# Power_Management.net
KiCad netlist of a schematic drawn in Altium Designer
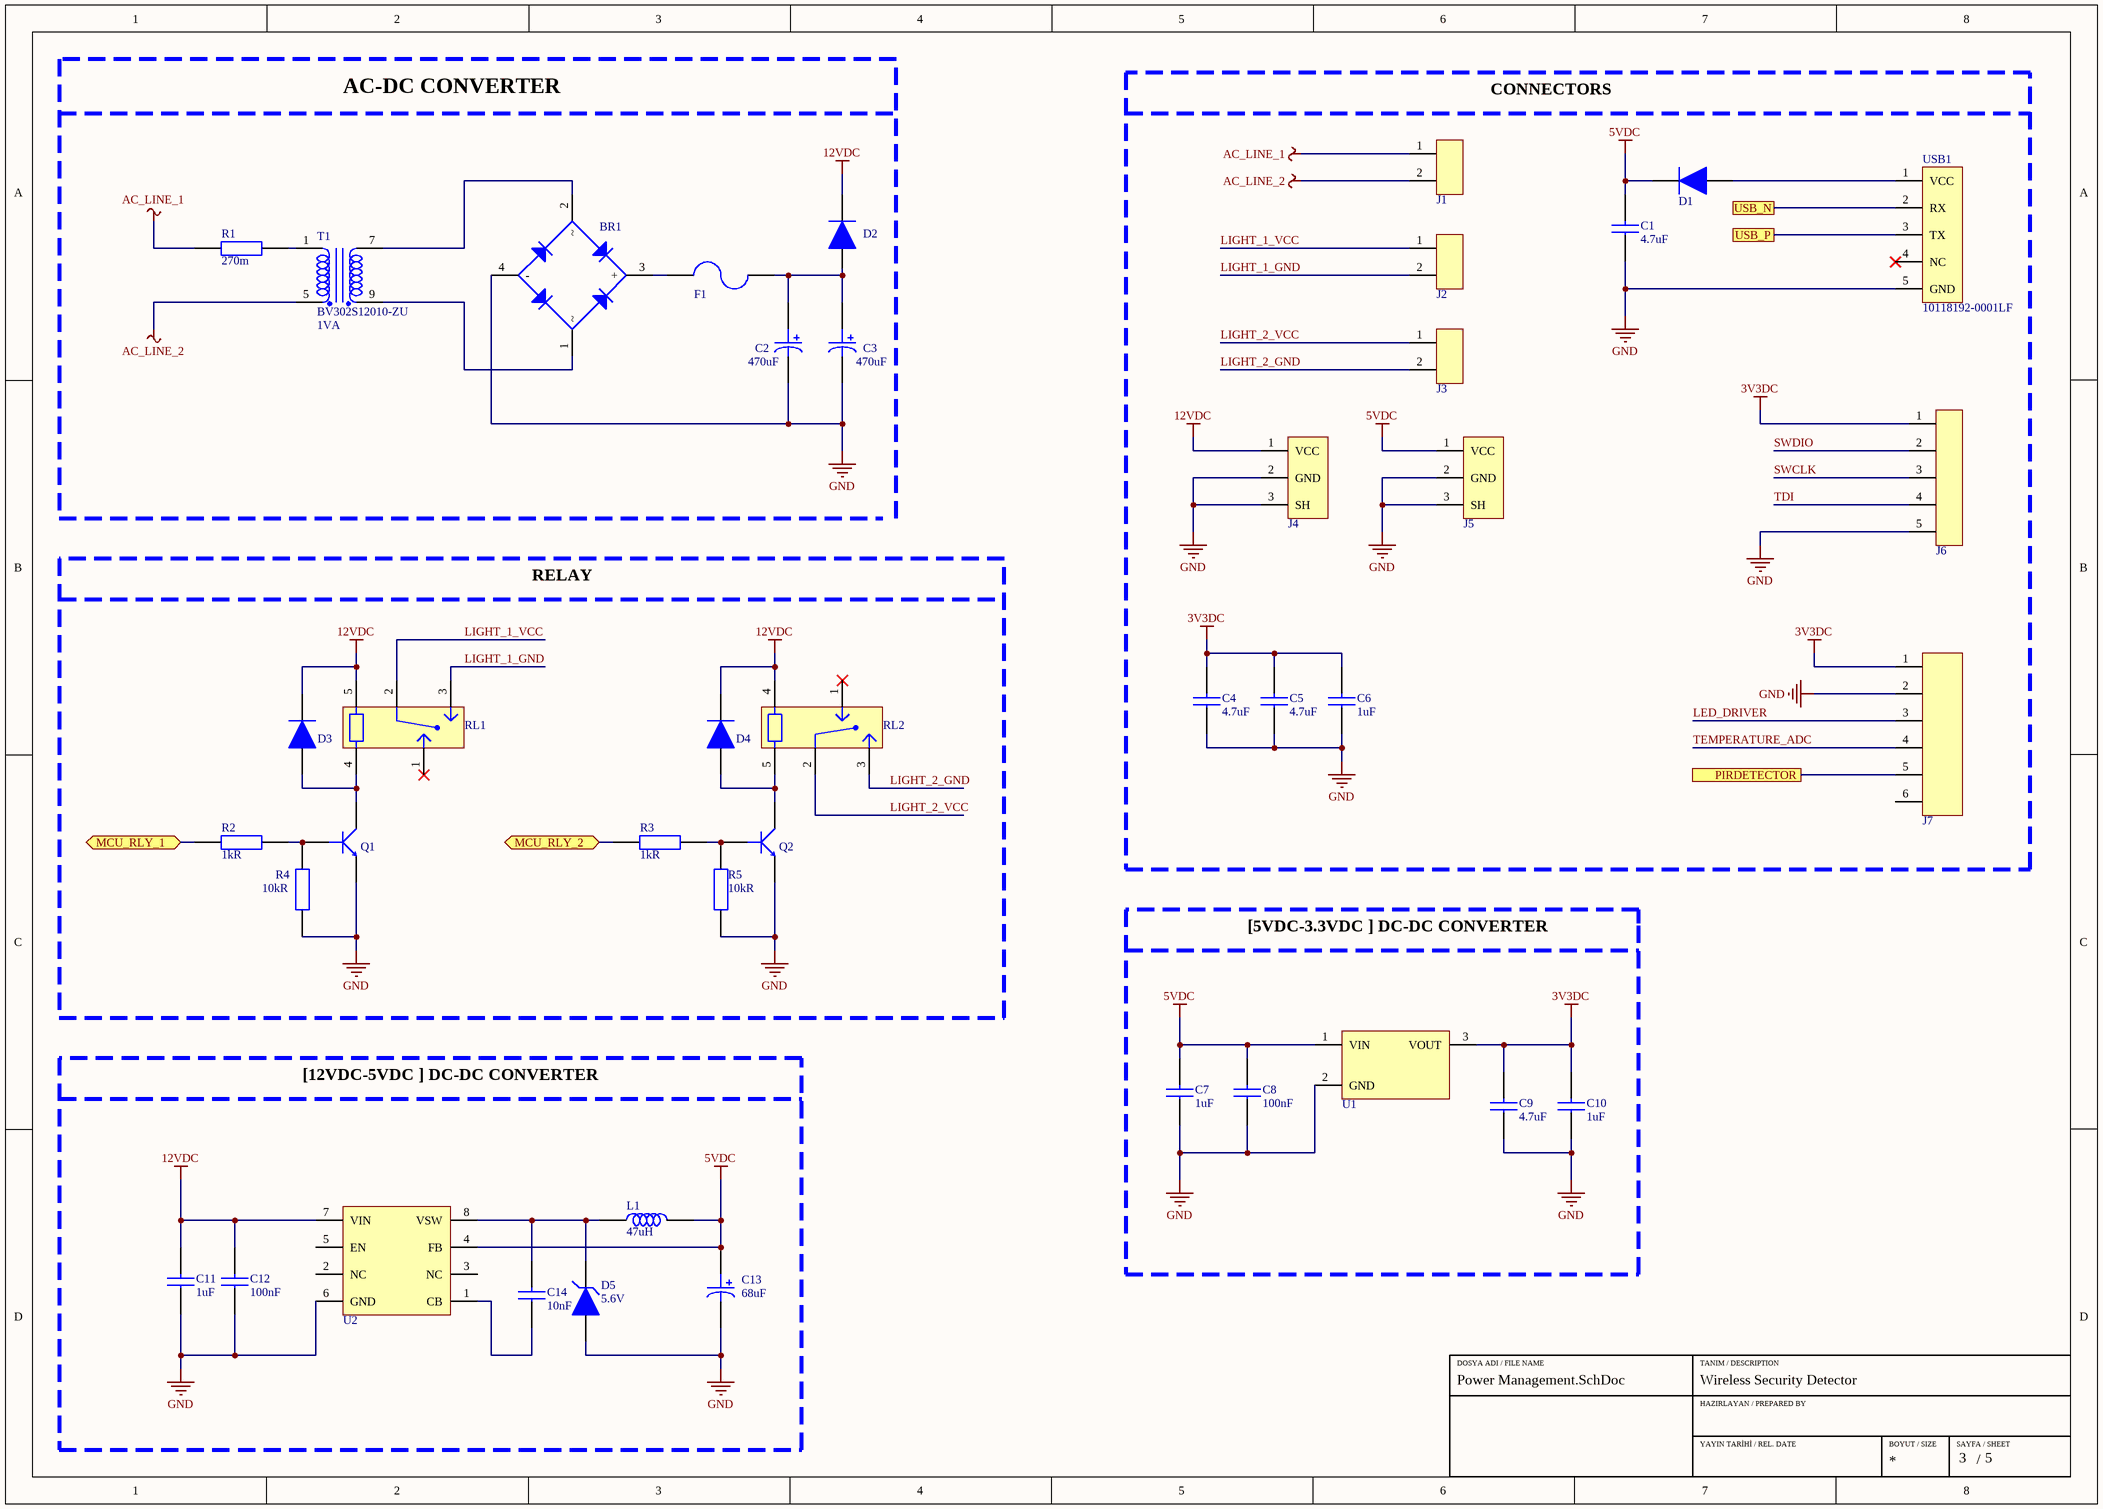
[diagram p0: Power Management.SchDoc]

(export (version "E")
  (design (tool "Eeschema 10.0.6"))
  (components
    (comp (ref "BR1")
      (value "DB105STR")
      (footprint "DB105STR")
      (description "Bridge Diode AC-DC")
      (fields (field (name "MANUFACTURER") "Sangdest Microelectronics") (field (name "DESIGNED BY") "BERK"))
      (libsource (lib "SECURITY_CAM") (part "DB105STR"))
    )
    (comp (ref "C1")
      (value "CL21A475KAQNNNE")
      (footprint "CAP_0805")
      (description "CAP CER 4.7uF %10 0805")
      (fields
        (field (name "MANUFACTURER") "Samsung")
        (field (name "TOLERANCE") "10%")
        (field (name "CAPACITANCE") "4.7uF")
        (field (name "DESIGNED BY") "BERK")
      )
      (libsource (lib "SECURITY_CAM") (part "CAP CER 4.7uF 0805"))
    )
    (comp (ref "C2")
      (value "ESH477M050AH4AA")
      (footprint "CAP_RADIAL_D10_P5")
      (description "CAP ALU ELEC 470uF 50V RADIAL")
      (fields
        (field (name "MANUFACTURER") "KEMET")
        (field (name "TOLERANCE") "20%")
        (field (name "CAPACITANCE") "470uF")
        (field (name "DESIGNED BY") "BERK")
      )
      (libsource (lib "SECURITY_CAM") (part "CAP ALU ELEC 470uF 50V"))
    )
    (comp (ref "C3")
      (value "ESH477M050AH4AA")
      (footprint "CAP_RADIAL_D10_P5")
      (description "CAP ALU ELEC 470uF 50V RADIAL")
      (fields
        (field (name "MANUFACTURER") "KEMET")
        (field (name "TOLERANCE") "20%")
        (field (name "CAPACITANCE") "470uF")
        (field (name "DESIGNED BY") "BERK")
      )
      (libsource (lib "SECURITY_CAM") (part "CAP ALU ELEC 470uF 50V"))
    )
    (comp (ref "C4")
      (value "CL21A475KAQNNNE")
      (footprint "CAP_0805")
      (description "CAP CER 4.7uF %10 0805")
      (fields
        (field (name "MANUFACTURER") "Samsung")
        (field (name "TOLERANCE") "10%")
        (field (name "CAPACITANCE") "4.7uF")
        (field (name "DESIGNED BY") "BERK")
      )
      (libsource (lib "SECURITY_CAM") (part "CAP CER 4.7uF 0805"))
    )
    (comp (ref "C5")
      (value "CL21A475KAQNNNE")
      (footprint "CAP_0805")
      (description "CAP CER 4.7uF %10 0805")
      (fields
        (field (name "MANUFACTURER") "Samsung")
        (field (name "TOLERANCE") "10%")
        (field (name "CAPACITANCE") "4.7uF")
        (field (name "DESIGNED BY") "BERK")
      )
      (libsource (lib "SECURITY_CAM") (part "CAP CER 4.7uF 0805"))
    )
    (comp (ref "C6")
      (value "CL21B105KBFNNNE")
      (footprint "CAP_0805")
      (description "CAP CER 1uF %10 0805")
      (fields
        (field (name "MANUFACTURER") "Samsung")
        (field (name "TOLERANCE") "10%")
        (field (name "CAPACITANCE") "1uF")
        (field (name "DESIGNED BY") "BERK")
      )
      (libsource (lib "SECURITY_CAM") (part "CAP CER 1uF 0805"))
    )
    (comp (ref "C7")
      (value "CL21B105KBFNNNE")
      (footprint "CAP_0805")
      (description "CAP CER 1uF %10 0805")
      (fields
        (field (name "MANUFACTURER") "Samsung")
        (field (name "TOLERANCE") "10%")
        (field (name "CAPACITANCE") "1uF")
        (field (name "DESIGNED BY") "BERK")
      )
      (libsource (lib "SECURITY_CAM") (part "CAP CER 1uF 0805"))
    )
    (comp (ref "C8")
      (value "C0603C104K5RACTU")
      (footprint "CAP_0603")
      (description "CAP CER 100nF %10 0603 SMD")
      (fields
        (field (name "MANUFACTURER") "KEMET")
        (field (name "TOLERANCE") "10%")
        (field (name "CAPACITANCE") "100nF")
        (field (name "DESIGNED BY") "BERK")
      )
      (libsource (lib "SECURITY_CAM") (part "CAP CER 100nF 0603"))
    )
    (comp (ref "C9")
      (value "CL21A475KAQNNNE")
      (footprint "CAP_0805")
      (description "CAP CER 4.7uF %10 0805")
      (fields
        (field (name "MANUFACTURER") "Samsung")
        (field (name "TOLERANCE") "10%")
        (field (name "CAPACITANCE") "4.7uF")
        (field (name "DESIGNED BY") "BERK")
      )
      (libsource (lib "SECURITY_CAM") (part "CAP CER 4.7uF 0805"))
    )
    (comp (ref "C10")
      (value "CL21B105KBFNNNE")
      (footprint "CAP_0805")
      (description "CAP CER 1uF %10 0805")
      (fields
        (field (name "MANUFACTURER") "Samsung")
        (field (name "TOLERANCE") "10%")
        (field (name "CAPACITANCE") "1uF")
        (field (name "DESIGNED BY") "BERK")
      )
      (libsource (lib "SECURITY_CAM") (part "CAP CER 1uF 0805"))
    )
    (comp (ref "C11")
      (value "CL21B105KBFNNNE")
      (footprint "CAP_0805")
      (description "CAP CER 1uF %10 0805")
      (fields
        (field (name "MANUFACTURER") "Samsung")
        (field (name "TOLERANCE") "10%")
        (field (name "CAPACITANCE") "1uF")
        (field (name "DESIGNED BY") "BERK")
      )
      (libsource (lib "SECURITY_CAM") (part "CAP CER 1uF 0805"))
    )
    (comp (ref "C12")
      (value "CL21B104KBCNNNC")
      (footprint "CAP_0805")
      (description "CAP CER 100nF %10 0805")
      (fields
        (field (name "MANUFACTURER") "Samsung")
        (field (name "TOLERANCE") "10%")
        (field (name "CAPACITANCE") "100nF")
        (field (name "DESIGNED BY") "BERK")
      )
      (libsource (lib "SECURITY_CAM") (part "CAP CER 100nF 0805"))
    )
    (comp (ref "C13")
      (value "EEV686M035A9HAA")
      (footprint "CAP_EEVseries")
      (description "Cap Aluminum Lytic 68uF 35V 20% (6.3 X 7.7mm) SMD 280mA 2000h 105C T/R")
      (fields
        (field (name "MANUFACTURER") "KEMET")
        (field (name "TOLERANCE") "20%")
        (field (name "CAPACITANCE") "68uF")
      )
      (libsource (lib "SECURITY_CAM") (part "CAP ALU 68uF"))
    )
    (comp (ref "C14")
      (value "0603B103K160CT")
      (footprint "CAP_0603")
      (description "CAP CER 10nF %10 0603")
      (fields
        (field (name "MANUFACTURER") "Walsin Technologies")
        (field (name "TOLERANCE") "10%")
        (field (name "CAPACITANCE") "10nF")
        (field (name "DESIGNED BY") "BERK")
      )
      (libsource (lib "SECURITY_CAM") (part "CAP CER 10nF 0603"))
    )
    (comp (ref "D1")
      (value "1N4148WS")
      (footprint "SOD323F")
      (description "Diode, Single, 75 V, 150 mA, 1 V, 4 ns")
      (fields
        (field (name "MANUFACTURER") "ON Semiconductor / Fairchild")
        (field (name "DESIGNED BY") "BERK")
      )
      (libsource (lib "SECURITY_CAM") (part "1N4148WS"))
    )
    (comp (ref "D2")
      (value "1N4148WS")
      (footprint "SOD323F")
      (description "Diode, Single, 75 V, 150 mA, 1 V, 4 ns")
      (fields
        (field (name "MANUFACTURER") "ON Semiconductor / Fairchild")
        (field (name "DESIGNED BY") "BERK")
      )
      (libsource (lib "SECURITY_CAM") (part "1N4148WS"))
    )
    (comp (ref "D3")
      (value "1N4148WS")
      (footprint "SOD323F")
      (description "Diode, Single, 75 V, 150 mA, 1 V, 4 ns")
      (fields
        (field (name "MANUFACTURER") "ON Semiconductor / Fairchild")
        (field (name "DESIGNED BY") "BERK")
      )
      (libsource (lib "SECURITY_CAM") (part "1N4148WS"))
    )
    (comp (ref "D4")
      (value "1N4148WS")
      (footprint "SOD323F")
      (description "Diode, Single, 75 V, 150 mA, 1 V, 4 ns")
      (fields
        (field (name "MANUFACTURER") "ON Semiconductor / Fairchild")
        (field (name "DESIGNED BY") "BERK")
      )
      (libsource (lib "SECURITY_CAM") (part "1N4148WS"))
    )
    (comp (ref "D5")
      (value "1SMB5919BT3G")
      (footprint "SMB")
      (description "Diode Zener Single 5.6V 5% 3W 2-Pin SMB T/R")
      (fields
        (field (name "MANUFACTURER") "ON Semiconductor")
        (field (name "TOLERANCE") "5%")
        (field (name "WORKING VOLTAGE") "5.6V")
        (field (name "DESIGNED BY") "BERK")
      )
      (libsource (lib "SECURITY_CAM") (part "1SMB5919BT3G"))
    )
    (comp (ref "F1")
      (value "3413.0216.22")
      (footprint "3413.0216.22")
      (description "FUSE BRD MNT 1A 32VAC 63VDC 1206")
      (fields (field (name "MANUFACTURER") "Schurter") (field (name "DESIGNED BY") "BERK"))
      (libsource (lib "SECURITY_CAM") (part "FUSE 3413.0216.22"))
    )
    (comp (ref "J1")
      (value "TBP01R1-508-02BE")
      (footprint "TBP01R1-508")
      (description "Conn Shrouded Header HDR 2 POS 5.08mm Solder RA Side Entry Thru-Hole Bag")
      (fields (field (name "MANUFACTURER") "CUI") (field (name "DESIGNED BY") "BERK"))
      (libsource (lib "SECURITY_CAM") (part "TBP01R1-508-02BE"))
    )
    (comp (ref "J2")
      (value "TBP01R1-508-02BE")
      (footprint "TBP01R1-508")
      (description "Conn Shrouded Header HDR 2 POS 5.08mm Solder RA Side Entry Thru-Hole Bag")
      (fields (field (name "MANUFACTURER") "CUI") (field (name "DESIGNED BY") "BERK"))
      (libsource (lib "SECURITY_CAM") (part "TBP01R1-508-02BE"))
    )
    (comp (ref "J3")
      (value "TBP01R1-508-02BE")
      (footprint "TBP01R1-508")
      (description "Conn Shrouded Header HDR 2 POS 5.08mm Solder RA Side Entry Thru-Hole Bag")
      (fields (field (name "MANUFACTURER") "CUI") (field (name "DESIGNED BY") "BERK"))
      (libsource (lib "SECURITY_CAM") (part "TBP01R1-508-02BE"))
    )
    (comp (ref "J4")
      (value "PJ-037AH-SMT-TR")
      (footprint "JACK")
      (description "DC Power Connectors Power Jacks")
      (fields (field (name "MANUFACTURER") "CUI") (field (name "DESIGNED BY") "BERK"))
      (libsource (lib "SECURITY_CAM") (part "PJ-037AH-SMT-TR"))
    )
    (comp (ref "J5")
      (value "PJ-037AH-SMT-TR")
      (footprint "JACK")
      (description "DC Power Connectors Power Jacks")
      (fields (field (name "MANUFACTURER") "CUI") (field (name "DESIGNED BY") "BERK"))
      (libsource (lib "SECURITY_CAM") (part "PJ-037AH-SMT-TR"))
    )
    (comp (ref "J6")
      (value "SMH-105-02-L-S")
      (footprint "PINHEADER1X5_RA")
      (description ".100 C.L. HORIZONTAL SMT SOCKET")
      (fields (field (name "MANUFACTURER") "Samtec") (field (name "DESIGNED BY") "BERK"))
      (libsource (lib "SECURITY_CAM") (part "SMH-105-02-L-S"))
    )
    (comp (ref "J7")
      (value "64800611622")
      (footprint "64800611622")
      (description "1.50mm 6PIN Connector")
      (fields (field (name "MANUFACTURER") "Wurth Electronics"))
      (libsource (lib "SECURITY_CAM") (part "64800611622_conn_6pin"))
    )
    (comp (ref "L1")
      (value "78438335470")
      (footprint "IND_1212")
      (description "FIXED IND 47UH 390MA 2.3 OHM SMD")
      (fields
        (field (name "MANUFACTURER") "Wurth Electronics")
        (field (name "TOLERANCE") "30%")
        (field (name "INDUCTANCE") "47uH")
        (field (name "DESIGNED BY") "BERK")
      )
      (libsource (lib "SECURITY_CAM") (part "IND 47uH"))
    )
    (comp (ref "Q1")
      (value "MMBT3904-7-F")
      (footprint "SOT-23F")
      (description "Transistor General Purpose BJT NPN 40 Volt 0.2A Automotive 3-Pin SOT-23")
      (fields (field (name "MANUFACTURER") "Diodes Zetex") (field (name "DESIGNED BY") "BERK"))
      (libsource (lib "SECURITY_CAM") (part "MMBT3904-7-F"))
    )
    (comp (ref "Q2")
      (value "MMBT3904-7-F")
      (footprint "SOT-23F")
      (description "Transistor General Purpose BJT NPN 40 Volt 0.2A Automotive 3-Pin SOT-23")
      (fields (field (name "MANUFACTURER") "Diodes Zetex") (field (name "DESIGNED BY") "BERK"))
      (libsource (lib "SECURITY_CAM") (part "MMBT3904-7-F"))
    )
    (comp (ref "R1")
      (value "5WD27")
      (footprint "RES_AXIAL_W")
      (description "Resistor 5 Watt Cermet Wirewound Flameproof .27 Ohm 5% Axial Lead")
      (fields
        (field (name "MANUFACTURER") "NTE Electronics")
        (field (name "TOLERANCE") "5%")
        (field (name "RESISTANCE") "270m")
        (field (name "DESIGNED BY") "BERK")
      )
      (libsource (lib "SECURITY_CAM") (part "5WD27"))
    )
    (comp (ref "R2")
      (value "RC0603FR-0710KL")
      (footprint "RES_0603")
      (description "RES 1K %1 OHM 0603 SMD")
      (fields
        (field (name "MANUFACTURER") "Yageo")
        (field (name "MANUFACTURER PART NUMBER") "RC0603JR-071KL")
        (field (name "RESISTANCE") "1kR")
        (field (name "DESIGNED BY") "BERK")
      )
      (libsource (lib "SECURITY_CAM") (part "RES 1K OHM 0603"))
    )
    (comp (ref "R3")
      (value "RC0603FR-0710KL")
      (footprint "RES_0603")
      (description "RES 1K %1 OHM 0603 SMD")
      (fields
        (field (name "MANUFACTURER") "Yageo")
        (field (name "MANUFACTURER PART NUMBER") "RC0603JR-071KL")
        (field (name "RESISTANCE") "1kR")
        (field (name "DESIGNED BY") "BERK")
      )
      (libsource (lib "SECURITY_CAM") (part "RES 1K OHM 0603"))
    )
    (comp (ref "R4")
      (value "RC0603FR-0710KL")
      (footprint "RES_0603")
      (description "RES 10K %1 OHM 0603 SMD")
      (fields
        (field (name "MANUFACTURER") "Yageo")
        (field (name "TOLERANCE") "1%")
        (field (name "RESISTANCE") "10kR")
        (field (name "DESIGNED BY") "BERK")
      )
      (libsource (lib "SECURITY_CAM") (part "RES 10K OHM 0603"))
    )
    (comp (ref "R5")
      (value "RC0603FR-0710KL")
      (footprint "RES_0603")
      (description "RES 10K %1 OHM 0603 SMD")
      (fields
        (field (name "MANUFACTURER") "Yageo")
        (field (name "TOLERANCE") "1%")
        (field (name "RESISTANCE") "10kR")
        (field (name "DESIGNED BY") "BERK")
      )
      (libsource (lib "SECURITY_CAM") (part "RES 10K OHM 0603"))
    )
    (comp (ref "RL1")
      (value "ALQ112")
      (footprint "ALQ112")
      (description "General Purpose Relay SPDT (1 Form C) 12VDC Coil Through Hole")
      (fields (field (name "MANUFACTURER") "Panasonic") (field (name "DESIGNED BY") "BERK"))
      (libsource (lib "SECURITY_CAM") (part "ALQ112"))
    )
    (comp (ref "RL2")
      (value "ALQ112")
      (footprint "ALQ112")
      (description "General Purpose Relay SPDT (1 Form C) 12VDC Coil Through Hole")
      (fields (field (name "MANUFACTURER") "Panasonic") (field (name "DESIGNED BY") "BERK"))
      (libsource (lib "") (part "ALQ112_1"))
    )
    (comp (ref "T1")
      (value "BV302S12010-ZU")
      (footprint "BV302S")
      (description "230-12 Transformer 1VA")
      (fields
        (field (name "MANUFACTURER") "Zettler Magnetics")
        (field (name "RATED POWER") "1VA")
        (field (name "DESIGNED BY") "BERK")
      )
      (libsource (lib "SECURITY_CAM") (part "BV302S12010-ZU"))
    )
    (comp (ref "U1")
      (value "AP7361-33E-13")
      (footprint "SOT223")
      (description "LDO Regulator Pos 3.3V 1A 4-Pin(3+Tab) SOT-223 T/R")
      (fields (field (name "MANUFACTURER") "Diodes") (field (name "DESIGNED BY") "BERK"))
      (libsource (lib "SECURITY_CAM") (part "AP7361-33E-13"))
    )
    (comp (ref "U2")
      (value "LM2675MX-12/NOPB")
      (footprint "SOIC8")
      (description "Switching Voltage Regulators Pwr Cnvtr Hi Eff 1A SD Vtg Reg")
      (fields (field (name "MANUFACTURER") "TI National Semiconductor") (field (name "DESIGNED BY") "BERK"))
      (libsource (lib "SECURITY_CAM") (part "LM2675MX-12/NOPB"))
    )
    (comp (ref "USB1")
      (value "10118192-0001LF")
      (footprint "MICRO_B_USB")
      (description "CONN RCPT USB2.0 MICRO B SMD R/A")
      (fields (field (name "MANUFACTURER") "Amphenol FCI") (field (name "DESIGNED BY") "BERK"))
      (libsource (lib "SECURITY_CAM") (part "Micro B USB Connector"))
    )
  )
  (nets
    (net (code "1") (name "/LED_DRIVER") (class "Default") (node (ref "J7") (pin "3") (pintype "power_in")))
    (net (code "2") (name "/LIGHT_1_GND") (class "Default")
      (node (ref "J2") (pin "2") (pinfunction "2_2") (pintype "power_in"))
      (node (ref "RL1") (pin "3") (pinfunction "3_3") (pintype "passive"))
    )
    (net (code "3") (name "/LIGHT_1_VCC") (class "Default")
      (node (ref "J2") (pin "1") (pinfunction "1_1") (pintype "power_in"))
      (node (ref "RL1") (pin "2") (pinfunction "2_2") (pintype "passive"))
    )
    (net (code "4") (name "/LIGHT_2_GND") (class "Default")
      (node (ref "J3") (pin "2") (pinfunction "2_2") (pintype "power_in"))
      (node (ref "RL2") (pin "3") (pinfunction "3_3") (pintype "passive"))
    )
    (net (code "5") (name "/LIGHT_2_VCC") (class "Default")
      (node (ref "J3") (pin "1") (pinfunction "1_1") (pintype "power_in"))
      (node (ref "RL2") (pin "2") (pinfunction "2_2") (pintype "passive"))
    )
    (net (code "6") (name "/MCU_RLY_1") (class "Default")
      (node (ref "R2") (pin "1") (pinfunction "1_1") (pintype "passive"))
    )
    (net (code "7") (name "/MCU_RLY_2") (class "Default")
      (node (ref "R3") (pin "1") (pinfunction "1_1") (pintype "passive"))
    )
    (net (code "8") (name "/PIRDETECTOR") (class "Default") (node (ref "J7") (pin "5") (pintype "power_in")))
    (net (code "9") (name "/SWCLK") (class "Default")
      (node (ref "J6") (pin "3") (pinfunction "3_3") (pintype "power_in"))
    )
    (net (code "10") (name "/SWDIO") (class "Default")
      (node (ref "J6") (pin "2") (pinfunction "2_2") (pintype "power_in"))
    )
    (net (code "11") (name "/TDI") (class "Default")
      (node (ref "J6") (pin "4") (pinfunction "4_4") (pintype "power_in"))
    )
    (net (code "12") (name "/TEMPERATURE_ADC") (class "Default")
      (node (ref "J7") (pin "4") (pintype "power_in"))
    )
    (net (code "13") (name "/USB_N") (class "Default")
      (node (ref "USB1") (pin "2") (pinfunction "RX_2") (pintype "power_in"))
    )
    (net (code "14") (name "/USB_P") (class "Default")
      (node (ref "USB1") (pin "3") (pinfunction "TX_3") (pintype "power_in"))
    )
    (net (code "15") (name "3V3DC") (class "Default")
      (node (ref "C10") (pin "2") (pinfunction "2_2") (pintype "passive"))
      (node (ref "C4") (pin "2") (pinfunction "2_2") (pintype "passive"))
      (node (ref "C5") (pin "2") (pinfunction "2_2") (pintype "passive"))
      (node (ref "C6") (pin "2") (pinfunction "2_2") (pintype "passive"))
      (node (ref "C9") (pin "2") (pinfunction "2_2") (pintype "passive"))
      (node (ref "J6") (pin "1") (pinfunction "1_1") (pintype "power_in"))
      (node (ref "J7") (pin "1") (pintype "power_in"))
      (node (ref "U1") (pin "3") (pinfunction "VOUT_3") (pintype "passive"))
    )
    (net (code "16") (name "5VDC") (class "Default")
      (node (ref "C1") (pin "2") (pinfunction "2_2") (pintype "passive"))
      (node (ref "C13") (pin "1") (pinfunction "1_1") (pintype "passive"))
      (node (ref "C7") (pin "2") (pinfunction "2_2") (pintype "passive"))
      (node (ref "C8") (pin "2") (pinfunction "2_2") (pintype "passive"))
      (node (ref "D1") (pin "1") (pinfunction "1_1") (pintype "power_in"))
      (node (ref "J5") (pin "1") (pinfunction "VCC_1") (pintype "power_in"))
      (node (ref "L1") (pin "2") (pinfunction "2_2") (pintype "passive"))
      (node (ref "U1") (pin "1") (pinfunction "VIN_1") (pintype "passive"))
      (node (ref "U2") (pin "4") (pinfunction "FB_4") (pintype "passive"))
    )
    (net (code "17") (name "12VDC") (class "Default")
      (node (ref "C11") (pin "2") (pinfunction "2_2") (pintype "passive"))
      (node (ref "C12") (pin "2") (pinfunction "2_2") (pintype "passive"))
      (node (ref "D2") (pin "1") (pinfunction "1_1") (pintype "power_in"))
      (node (ref "D3") (pin "1") (pinfunction "1_1") (pintype "power_in"))
      (node (ref "D4") (pin "1") (pinfunction "1_1") (pintype "power_in"))
      (node (ref "J4") (pin "1") (pinfunction "VCC_1") (pintype "power_in"))
      (node (ref "RL1") (pin "5") (pinfunction "5_5") (pintype "passive"))
      (node (ref "RL2") (pin "4") (pinfunction "4_4") (pintype "passive"))
      (node (ref "U2") (pin "7") (pinfunction "VIN_7") (pintype "passive"))
    )
    (net (code "18") (name "AC_LINE_1") (class "Default")
      (node (ref "J1") (pin "1") (pinfunction "1_1") (pintype "power_in"))
      (node (ref "R1") (pin "1") (pinfunction "1_1") (pintype "passive"))
    )
    (net (code "19") (name "AC_LINE_2") (class "Default")
      (node (ref "J1") (pin "2") (pinfunction "2_2") (pintype "power_in"))
      (node (ref "T1") (pin "5") (pinfunction "5_5") (pintype "passive"))
    )
    (net (code "20") (name "GND") (class "Default")
      (node (ref "BR1") (pin "4") (pinfunction "-_4") (pintype "passive"))
      (node (ref "C1") (pin "1") (pinfunction "1_1") (pintype "passive"))
      (node (ref "C10") (pin "1") (pinfunction "1_1") (pintype "passive"))
      (node (ref "C11") (pin "1") (pinfunction "1_1") (pintype "passive"))
      (node (ref "C12") (pin "1") (pinfunction "1_1") (pintype "passive"))
      (node (ref "C13") (pin "2") (pinfunction "2_2") (pintype "passive"))
      (node (ref "C2") (pin "2") (pinfunction "2_2") (pintype "passive"))
      (node (ref "C3") (pin "2") (pinfunction "2_2") (pintype "passive"))
      (node (ref "C4") (pin "1") (pinfunction "1_1") (pintype "passive"))
      (node (ref "C5") (pin "1") (pinfunction "1_1") (pintype "passive"))
      (node (ref "C6") (pin "1") (pinfunction "1_1") (pintype "passive"))
      (node (ref "C7") (pin "1") (pinfunction "1_1") (pintype "passive"))
      (node (ref "C8") (pin "1") (pinfunction "1_1") (pintype "passive"))
      (node (ref "C9") (pin "1") (pinfunction "1_1") (pintype "passive"))
      (node (ref "D5") (pin "A") (pinfunction "A_A") (pintype "passive"))
      (node (ref "J4") (pin "2") (pinfunction "GND_2") (pintype "power_in"))
      (node (ref "J4") (pin "3") (pinfunction "SH_3") (pintype "power_in"))
      (node (ref "J5") (pin "2") (pinfunction "GND_2") (pintype "power_in"))
      (node (ref "J5") (pin "3") (pinfunction "SH_3") (pintype "power_in"))
      (node (ref "J6") (pin "5") (pinfunction "5_5") (pintype "power_in"))
      (node (ref "J7") (pin "2") (pintype "power_in"))
      (node (ref "Q1") (pin "2") (pinfunction "E_2") (pintype "power_in"))
      (node (ref "Q2") (pin "2") (pinfunction "E_2") (pintype "power_in"))
      (node (ref "R4") (pin "1") (pinfunction "1_1") (pintype "passive"))
      (node (ref "R5") (pin "1") (pinfunction "1_1") (pintype "passive"))
      (node (ref "U1") (pin "2") (pinfunction "GND_2") (pintype "passive"))
      (node (ref "U2") (pin "6") (pinfunction "GND_6") (pintype "passive"))
      (node (ref "USB1") (pin "5") (pinfunction "GND_5") (pintype "power_in"))
    )
    (net (code "21") (name "Net-(BR1-+)") (class "Default")
      (node (ref "BR1") (pin "3") (pinfunction "+_3") (pintype "passive"))
      (node (ref "F1") (pin "1") (pinfunction "1_1") (pintype "passive"))
    )
    (net (code "22") (name "Net-(BR1-~-Pad1)") (class "Default")
      (node (ref "BR1") (pin "1") (pinfunction "~_1") (pintype "passive"))
      (node (ref "T1") (pin "9") (pinfunction "9_9") (pintype "passive"))
    )
    (net (code "23") (name "Net-(BR1-~-Pad2)") (class "Default")
      (node (ref "BR1") (pin "2") (pinfunction "~_2") (pintype "passive"))
      (node (ref "T1") (pin "7") (pinfunction "7_7") (pintype "passive"))
    )
    (net (code "24") (name "Net-(C2-Pad1)") (class "Default")
      (node (ref "C2") (pin "1") (pinfunction "1_1") (pintype "passive"))
      (node (ref "C3") (pin "1") (pinfunction "1_1") (pintype "passive"))
      (node (ref "D2") (pin "2") (pinfunction "2_2") (pintype "power_in"))
      (node (ref "F1") (pin "2") (pinfunction "2_2") (pintype "passive"))
    )
    (net (code "25") (name "Net-(Q1-B)") (class "Default")
      (node (ref "Q1") (pin "1") (pinfunction "B_1") (pintype "power_in"))
      (node (ref "R2") (pin "2") (pinfunction "2_2") (pintype "passive"))
      (node (ref "R4") (pin "2") (pinfunction "2_2") (pintype "passive"))
    )
    (net (code "26") (name "Net-(Q1-C)") (class "Default")
      (node (ref "D3") (pin "2") (pinfunction "2_2") (pintype "power_in"))
      (node (ref "Q1") (pin "3") (pinfunction "C_3") (pintype "power_in"))
      (node (ref "RL1") (pin "4") (pinfunction "4_4") (pintype "passive"))
    )
    (net (code "27") (name "Net-(Q2-B)") (class "Default")
      (node (ref "Q2") (pin "1") (pinfunction "B_1") (pintype "power_in"))
      (node (ref "R3") (pin "2") (pinfunction "2_2") (pintype "passive"))
      (node (ref "R5") (pin "2") (pinfunction "2_2") (pintype "passive"))
    )
    (net (code "28") (name "Net-(Q2-C)") (class "Default")
      (node (ref "D4") (pin "2") (pinfunction "2_2") (pintype "power_in"))
      (node (ref "Q2") (pin "3") (pinfunction "C_3") (pintype "power_in"))
      (node (ref "RL2") (pin "5") (pinfunction "5_5") (pintype "passive"))
    )
    (net (code "29") (name "Net-(R1-Pad2)") (class "Default")
      (node (ref "R1") (pin "2") (pinfunction "2_2") (pintype "passive"))
      (node (ref "T1") (pin "1") (pinfunction "1_1") (pintype "passive"))
    )
    (net (code "30") (name "Net-(U2-CB)") (class "Default")
      (node (ref "C14") (pin "1") (pinfunction "1_1") (pintype "passive"))
      (node (ref "U2") (pin "1") (pinfunction "CB_1") (pintype "passive"))
    )
    (net (code "31") (name "Net-(U2-VSW)") (class "Default")
      (node (ref "C14") (pin "2") (pinfunction "2_2") (pintype "passive"))
      (node (ref "D5") (pin "C") (pinfunction "C_C") (pintype "passive"))
      (node (ref "L1") (pin "1") (pinfunction "1_1") (pintype "passive"))
      (node (ref "U2") (pin "8") (pinfunction "VSW_8") (pintype "passive"))
    )
    (net (code "32") (name "Net-(USB1-VCC)") (class "Default")
      (node (ref "D1") (pin "2") (pinfunction "2_2") (pintype "power_in"))
      (node (ref "USB1") (pin "1") (pinfunction "VCC_1") (pintype "power_in"))
    )
    (net (code "33") (name "unconnected-(J7-Pad6)") (class "Default")
      (node (ref "J7") (pin "6") (pintype "power_in"))
    )
    (net (code "34") (name "unconnected-(RL1-Pad1)") (class "Default")
      (node (ref "RL1") (pin "1") (pinfunction "1_1") (pintype "passive+no_connect"))
    )
    (net (code "35") (name "unconnected-(RL2-Pad1)") (class "Default")
      (node (ref "RL2") (pin "1") (pinfunction "1_1") (pintype "passive+no_connect"))
    )
    (net (code "36") (name "unconnected-(U2-EN-Pad5)") (class "Default")
      (node (ref "U2") (pin "5") (pinfunction "EN_5") (pintype "passive"))
    )
    (net (code "37") (name "unconnected-(U2-NC-Pad2)") (class "Default")
      (node (ref "U2") (pin "2") (pinfunction "NC_2") (pintype "passive"))
    )
    (net (code "38") (name "unconnected-(U2-NC-Pad3)") (class "Default")
      (node (ref "U2") (pin "3") (pinfunction "NC_3") (pintype "passive"))
    )
    (net (code "39") (name "unconnected-(USB1-NC-Pad4)") (class "Default")
      (node (ref "USB1") (pin "4") (pinfunction "NC_4") (pintype "power_in+no_connect"))
    )
  )
)
